# 09_RS-232_EXT.net
KiCad netlist of a schematic drawn in Altium Designer
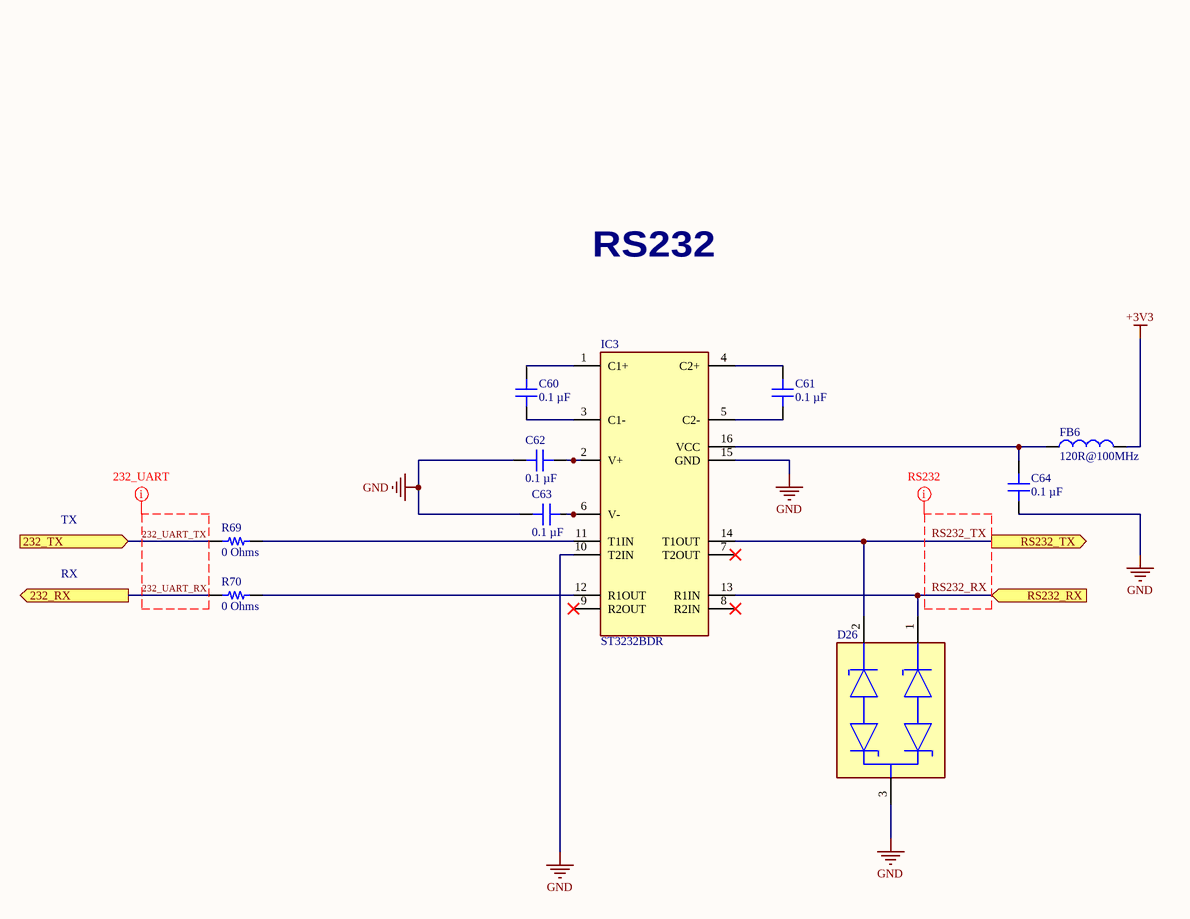
[diagram p0: 09_RS-232_EXT.SchDoc]

(export (version "E")
  (design (tool "Eeschema 10.0.6"))
  (components
    (comp (ref "C60")
      (value "0.1 µF")
      (footprint "CAP 0805_2012")
      (description "CAP CER 0.1UF 50V X8R 0805")
      (fields
        (field (name "PART NUMBER") "C2012X8R1H104K125AA")
        (field (name "MANUFACTURER") "TDK Corporation")
      )
      (libsource (lib "Celestial Altium Library - altium_library") (part "Capacitor"))
    )
    (comp (ref "C61")
      (value "0.1 µF")
      (footprint "CAP 0805_2012")
      (description "CAP CER 0.1UF 50V X8R 0805")
      (fields
        (field (name "PART NUMBER") "C2012X8R1H104K125AA")
        (field (name "MANUFACTURER") "TDK Corporation")
      )
      (libsource (lib "Celestial Altium Library - altium_library") (part "Capacitor"))
    )
    (comp (ref "C62")
      (value "0.1 µF")
      (footprint "CAP 0805_2012")
      (description "CAP CER 0.1UF 50V X8R 0805")
      (fields
        (field (name "PART NUMBER") "C2012X8R1H104K125AA")
        (field (name "MANUFACTURER") "TDK Corporation")
      )
      (libsource (lib "Celestial Altium Library - altium_library") (part "Capacitor"))
    )
    (comp (ref "C63")
      (value "0.1 µF")
      (footprint "CAP 0805_2012")
      (description "CAP CER 0.1UF 50V X8R 0805")
      (fields
        (field (name "PART NUMBER") "C2012X8R1H104K125AA")
        (field (name "MANUFACTURER") "TDK Corporation")
      )
      (libsource (lib "Celestial Altium Library - altium_library") (part "Capacitor"))
    )
    (comp (ref "C64")
      (value "0.1 µF")
      (footprint "CAP 0805_2012")
      (description "CAP CER 0.1UF 50V X8R 0805")
      (fields
        (field (name "PART NUMBER") "C2012X8R1H104K125AA")
        (field (name "MANUFACTURER") "TDK Corporation")
      )
      (libsource (lib "Celestial Altium Library - altium_library") (part "Capacitor"))
    )
    (comp (ref "D26")
      (value "PESD12VL2BT,215")
      (footprint "Nexperia_SOT23_0")
      (description "37V Clamp 5A (8/20µs) Ipp Tvs Diode Surface Mount TO-236AB")
      (fields (field (name "MANUFACTURER") "Nexperia USA Inc."))
      (libsource (lib "HW_HOLLAND_NCDM_MONITOR_R1") (part "PESD12VL2BT,215"))
    )
    (comp (ref "FB6")
      (value "120R@100MHz")
      (footprint "FB 0603(1608)")
      (description "120 Ohms @ 100 MHz 1 Power Line Ferrite Bead 0603 (1608 Metric) 3A 30mOhm")
      (fields
        (field (name "MANUFACTURER PART NUMBER") "BLM18KG121TH1D")
        (field (name "LCSC PART NUMBER") "C437404")
      )
      (libsource (lib "HW_HOLLAND_NCDM_MONITOR_R1") (part "FB0603_120R@100MHz"))
    )
    (comp (ref "IC3")
      (value "ST3232BDR")
      (footprint "SOIC127P600X175-16N - duplicate")
      (description "ST3232B Series 5.5 V 400 kbps Low Power RS-232 Drivers and Receiver - SOIC-16")
      (fields (field (name "MANUFACTURER") "STMicroelectronics"))
      (libsource (lib "HW_HOLLAND_NCDM_MONITOR_R1") (part "ST3232BDR"))
    )
    (comp (ref "R69")
      (value "0 Ohms")
      (footprint "RES 0402_1005")
      (description "RES 0 OHM JUMPER 1/8W 0402")
      (fields
        (field (name "PART NUMBER") "HCJ0402ZT0R00")
        (field (name "MANUFACTURER") "Stackpole Electronics Inc")
      )
      (libsource (lib "Celestial Altium Library - altium_library") (part "Resistor"))
    )
    (comp (ref "R70")
      (value "0 Ohms")
      (footprint "RES 0402_1005")
      (description "RES 0 OHM JUMPER 1/8W 0402")
      (fields
        (field (name "PART NUMBER") "HCJ0402ZT0R00")
        (field (name "MANUFACTURER") "Stackpole Electronics Inc")
      )
      (libsource (lib "Celestial Altium Library - altium_library") (part "Resistor"))
    )
  )
  (nets
    (net (code "1") (name "+3V3") (class "Default")
      (node (ref "FB6") (pin "2") (pinfunction "2_2") (pintype "passive"))
    )
    (net (code "2") (name "/232_UART_RX") (class "Default")
      (node (ref "R70") (pin "2") (pinfunction "2_2") (pintype "passive"))
    )
    (net (code "3") (name "/232_UART_TX") (class "Default")
      (node (ref "R69") (pin "2") (pinfunction "2_2") (pintype "passive"))
    )
    (net (code "4") (name "/RS232_RX") (class "Default")
      (node (ref "D26") (pin "1") (pinfunction "cathode_1_1") (pintype "passive"))
      (node (ref "IC3") (pin "13") (pinfunction "R1IN_13") (pintype "passive"))
    )
    (net (code "5") (name "/RS232_TX") (class "Default")
      (node (ref "D26") (pin "2") (pinfunction "cathode_2_2") (pintype "passive"))
      (node (ref "IC3") (pin "14") (pinfunction "T1OUT_14") (pintype "passive"))
    )
    (net (code "6") (name "GND") (class "Default")
      (node (ref "C62") (pin "2") (pinfunction "2_2") (pintype "passive"))
      (node (ref "C63") (pin "2") (pinfunction "2_2") (pintype "passive"))
      (node (ref "C64") (pin "2") (pinfunction "2_2") (pintype "passive"))
      (node (ref "D26") (pin "3") (pinfunction "double_cathode_3") (pintype "passive"))
      (node (ref "IC3") (pin "10") (pinfunction "T2IN_10") (pintype "passive"))
      (node (ref "IC3") (pin "15") (pinfunction "GND_15") (pintype "passive"))
    )
    (net (code "7") (name "Net-(IC3-C1+)") (class "Default")
      (node (ref "C60") (pin "2") (pinfunction "2_2") (pintype "passive"))
      (node (ref "IC3") (pin "1") (pinfunction "C1+_1") (pintype "passive"))
    )
    (net (code "8") (name "Net-(IC3-C1-)") (class "Default")
      (node (ref "C60") (pin "1") (pinfunction "1_1") (pintype "passive"))
      (node (ref "IC3") (pin "3") (pinfunction "C1-_3") (pintype "passive"))
    )
    (net (code "9") (name "Net-(IC3-C2+)") (class "Default")
      (node (ref "C61") (pin "2") (pinfunction "2_2") (pintype "passive"))
      (node (ref "IC3") (pin "4") (pinfunction "C2+_4") (pintype "passive"))
    )
    (net (code "10") (name "Net-(IC3-C2-)") (class "Default")
      (node (ref "C61") (pin "1") (pinfunction "1_1") (pintype "passive"))
      (node (ref "IC3") (pin "5") (pinfunction "C2-_5") (pintype "passive"))
    )
    (net (code "11") (name "Net-(IC3-R1OUT)") (class "Default")
      (node (ref "IC3") (pin "12") (pinfunction "R1OUT_12") (pintype "passive"))
      (node (ref "R70") (pin "1") (pinfunction "1_1") (pintype "passive"))
    )
    (net (code "12") (name "Net-(IC3-T1IN)") (class "Default")
      (node (ref "IC3") (pin "11") (pinfunction "T1IN_11") (pintype "passive"))
      (node (ref "R69") (pin "1") (pinfunction "1_1") (pintype "passive"))
    )
    (net (code "13") (name "Net-(IC3-V+)") (class "Default")
      (node (ref "C62") (pin "1") (pinfunction "1_1") (pintype "passive"))
      (node (ref "IC3") (pin "2") (pinfunction "V+_2") (pintype "passive"))
    )
    (net (code "14") (name "Net-(IC3-V-)") (class "Default")
      (node (ref "C63") (pin "1") (pinfunction "1_1") (pintype "passive"))
      (node (ref "IC3") (pin "6") (pinfunction "V-_6") (pintype "passive"))
    )
    (net (code "15") (name "Net-(IC3-VCC)") (class "Default")
      (node (ref "C64") (pin "1") (pinfunction "1_1") (pintype "passive"))
      (node (ref "FB6") (pin "1") (pinfunction "1_1") (pintype "passive"))
      (node (ref "IC3") (pin "16") (pinfunction "VCC_16") (pintype "passive"))
    )
    (net (code "16") (name "unconnected-(IC3-R2IN-Pad8)") (class "Default")
      (node (ref "IC3") (pin "8") (pinfunction "R2IN_8") (pintype "passive+no_connect"))
    )
    (net (code "17") (name "unconnected-(IC3-R2OUT-Pad9)") (class "Default")
      (node (ref "IC3") (pin "9") (pinfunction "R2OUT_9") (pintype "passive+no_connect"))
    )
    (net (code "18") (name "unconnected-(IC3-T2OUT-Pad7)") (class "Default")
      (node (ref "IC3") (pin "7") (pinfunction "T2OUT_7") (pintype "passive+no_connect"))
    )
  )
)
